# TeensyLED.net
KiCad netlist of a schematic drawn in EAGLE
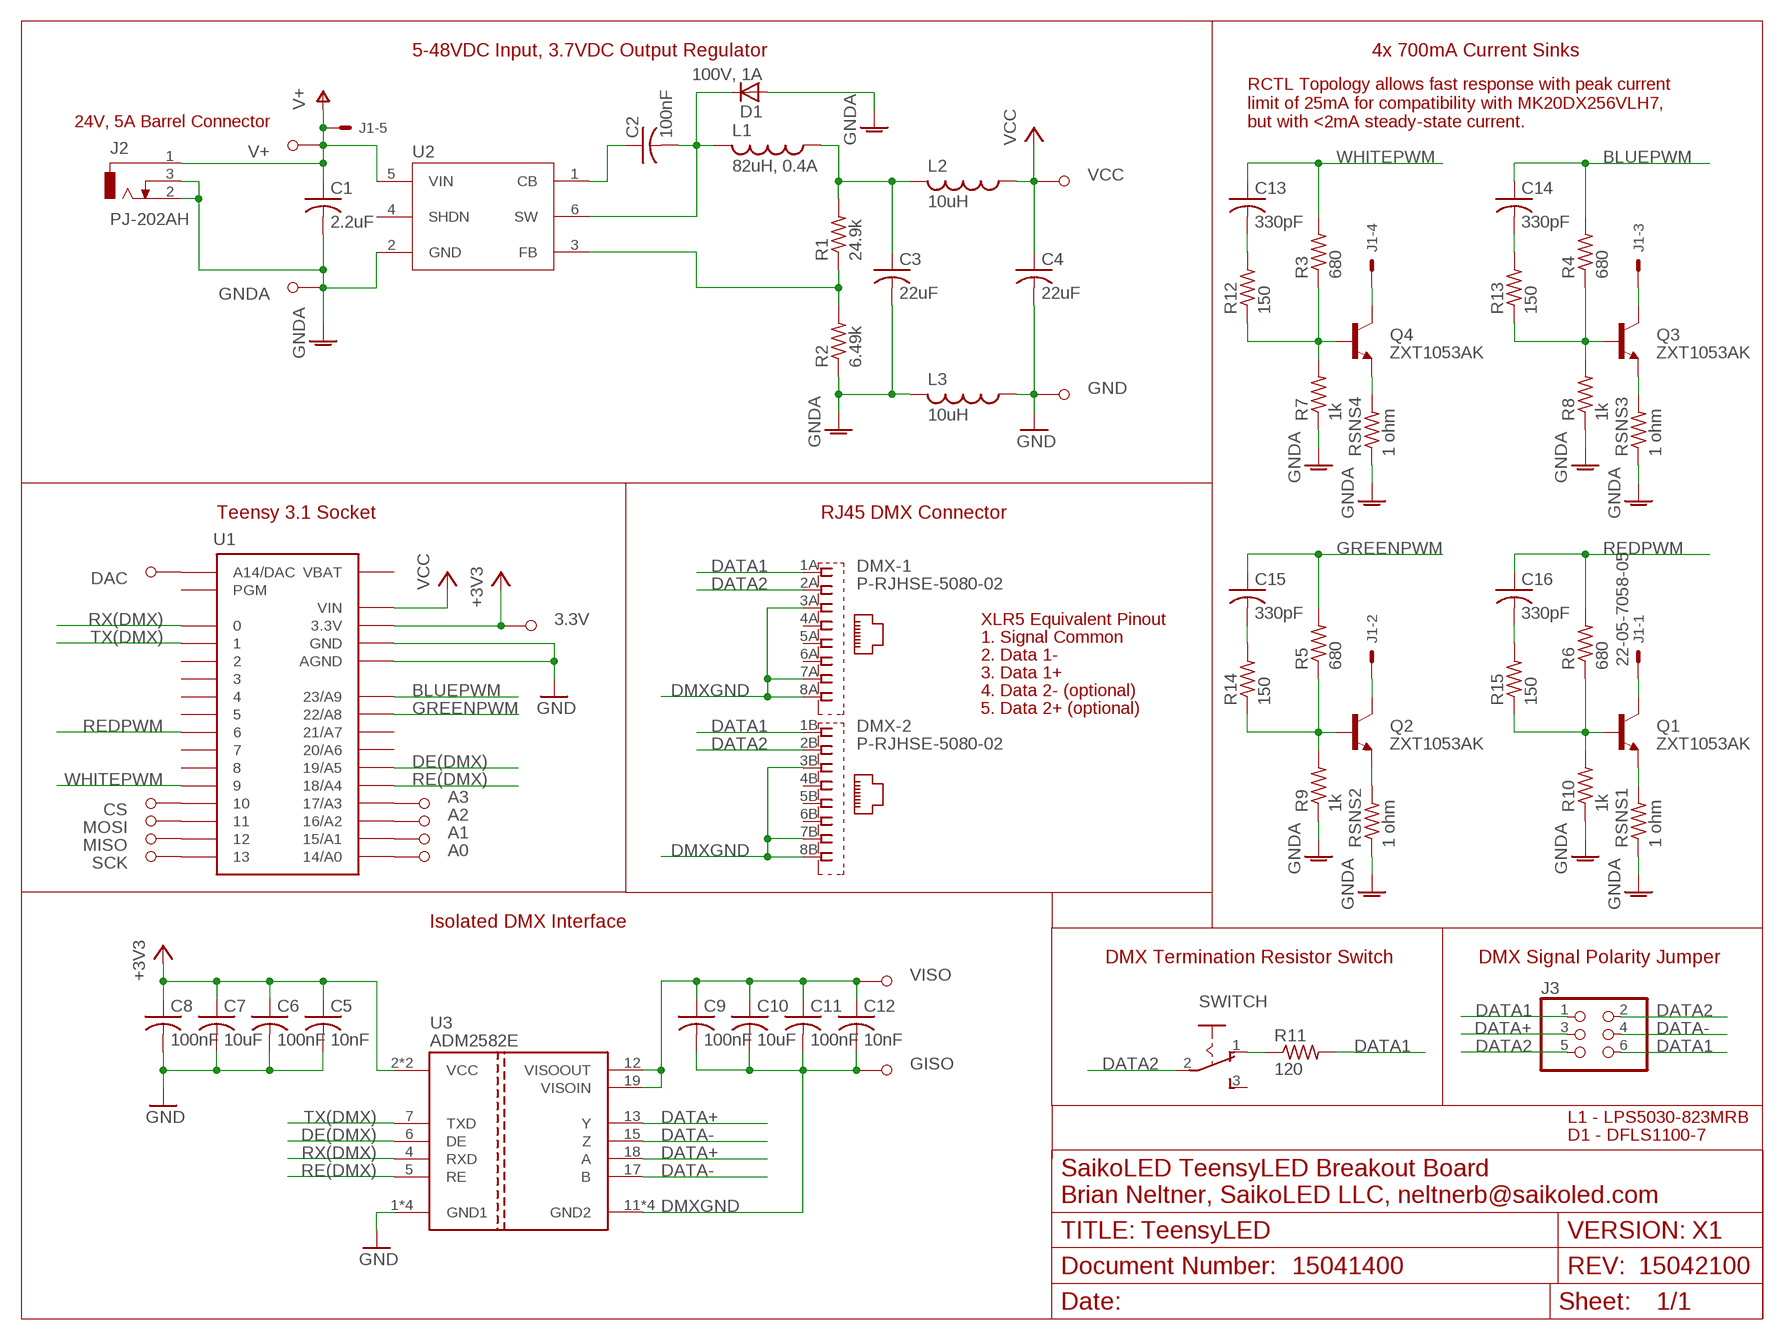
[diagram p0: schematic, sheet 1]

(export (version "E")
  (design (tool "Eeschema 10.0.6"))
  (components
    (comp (ref "3.3V")
      (value "TESTPOINT5019")
      (footprint "eagle-import:5019")
      (libsource (lib "eagle-import") (part "TESTPOINT5019"))
    )
    (comp (ref "A0")
      (value "TESTPOINT5019")
      (footprint "eagle-import:5019")
      (libsource (lib "eagle-import") (part "TESTPOINT5019"))
    )
    (comp (ref "A1")
      (value "TESTPOINT5019")
      (footprint "eagle-import:5019")
      (libsource (lib "eagle-import") (part "TESTPOINT5019"))
    )
    (comp (ref "A2")
      (value "TESTPOINT5019")
      (footprint "eagle-import:5019")
      (libsource (lib "eagle-import") (part "TESTPOINT5019"))
    )
    (comp (ref "A3")
      (value "TESTPOINT5019")
      (footprint "eagle-import:5019")
      (libsource (lib "eagle-import") (part "TESTPOINT5019"))
    )
    (comp (ref "C1")
      (value "2.2uF")
      (footprint "eagle-import:C1210K")
      (libsource (lib "eagle-import") (part "C-USC1210K"))
    )
    (comp (ref "C2")
      (value "100nF")
      (footprint "eagle-import:C0805K")
      (libsource (lib "eagle-import") (part "C-USC0805K"))
    )
    (comp (ref "C3")
      (value "22uF")
      (footprint "eagle-import:C0805K")
      (fields (field (name "MF") "Multicomp Passives") (field (name "MPN") "MCLV4R7M1HB-0513-RH"))
      (libsource (lib "eagle-import") (part "C-USC0805K"))
    )
    (comp (ref "C4")
      (value "22uF")
      (footprint "eagle-import:C0805K")
      (libsource (lib "eagle-import") (part "C-USC0805K"))
    )
    (comp (ref "C5")
      (value "10nF")
      (footprint "eagle-import:C0402PRO")
      (libsource (lib "eagle-import") (part "C-USC0402PRO"))
    )
    (comp (ref "C6")
      (value "100nF")
      (footprint "eagle-import:C0402PRO")
      (libsource (lib "eagle-import") (part "C-USC0402PRO"))
    )
    (comp (ref "C7")
      (value "10uF")
      (footprint "eagle-import:C0402PRO")
      (libsource (lib "eagle-import") (part "C-USC0402PRO"))
    )
    (comp (ref "C8")
      (value "100nF")
      (footprint "eagle-import:C0402PRO")
      (libsource (lib "eagle-import") (part "C-USC0402PRO"))
    )
    (comp (ref "C9")
      (value "100nF")
      (footprint "eagle-import:C0402PRO")
      (libsource (lib "eagle-import") (part "C-USC0402PRO"))
    )
    (comp (ref "C10")
      (value "10uF")
      (footprint "eagle-import:C0402PRO")
      (libsource (lib "eagle-import") (part "C-USC0402PRO"))
    )
    (comp (ref "C11")
      (value "100nF")
      (footprint "eagle-import:C0402PRO")
      (libsource (lib "eagle-import") (part "C-USC0402PRO"))
    )
    (comp (ref "C12")
      (value "10nF")
      (footprint "eagle-import:C0402PRO")
      (libsource (lib "eagle-import") (part "C-USC0402PRO"))
    )
    (comp (ref "C13")
      (value "330pF")
      (footprint "eagle-import:C0402PRO")
      (libsource (lib "eagle-import") (part "C-USC0402PRO"))
    )
    (comp (ref "C14")
      (value "330pF")
      (footprint "eagle-import:C0402PRO")
      (libsource (lib "eagle-import") (part "C-USC0402PRO"))
    )
    (comp (ref "C15")
      (value "330pF")
      (footprint "eagle-import:C0402PRO")
      (libsource (lib "eagle-import") (part "C-USC0402PRO"))
    )
    (comp (ref "C16")
      (value "330pF")
      (footprint "eagle-import:C0402PRO")
      (libsource (lib "eagle-import") (part "C-USC0402PRO"))
    )
    (comp (ref "CS")
      (value "TESTPOINT5019")
      (footprint "eagle-import:5019")
      (libsource (lib "eagle-import") (part "TESTPOINT5019"))
    )
    (comp (ref "D1")
      (value "100V, 1A")
      (footprint "eagle-import:DFLS1100")
      (libsource (lib "eagle-import") (part "DFLS1100"))
    )
    (comp (ref "DAC")
      (value "TESTPOINT5019")
      (footprint "eagle-import:5019")
      (libsource (lib "eagle-import") (part "TESTPOINT5019"))
    )
    (comp (ref "DMX")
      (value "P-RJHSE-5080-02")
      (footprint "eagle-import:P-RJHSE-5080-02")
      (libsource (lib "eagle-import") (part "P-RJHSE-5080-02"))
    )
    (comp (ref "FRAME1")
      (value "LETTER_L")
      (footprint "eagle-import:PCBINFO")
      (libsource (lib "eagle-import") (part "LETTER_L"))
    )
    (comp (ref "GISO")
      (value "TESTPOINT5019")
      (footprint "eagle-import:5019")
      (libsource (lib "eagle-import") (part "TESTPOINT5019"))
    )
    (comp (ref "GND")
      (value "TESTPOINT5019")
      (footprint "eagle-import:5019")
      (libsource (lib "eagle-import") (part "TESTPOINT5019"))
    )
    (comp (ref "GNDA")
      (value "TESTPOINT5019")
      (footprint "eagle-import:5019")
      (libsource (lib "eagle-import") (part "TESTPOINT5019"))
    )
    (comp (ref "J1")
      (value "22-05-7058-05")
      (footprint "eagle-import:7395-05")
      (libsource (lib "eagle-import") (part "22-?-0505-7058"))
    )
    (comp (ref "J2")
      (value "PJ-202AH")
      (footprint "eagle-import:PJ-202AH")
      (libsource (lib "eagle-import") (part "PJ-202AH"))
    )
    (comp (ref "J3")
      (value "PINHD-2X3")
      (footprint "eagle-import:2X03")
      (libsource (lib "eagle-import") (part "PINHD-2X3"))
    )
    (comp (ref "L1")
      (value "82uH, 0.4A")
      (footprint "eagle-import:LPS5030")
      (libsource (lib "eagle-import") (part "L-US"))
    )
    (comp (ref "L2")
      (value "10uH")
      (footprint "eagle-import:L2012C")
      (libsource (lib "eagle-import") (part "rcl_L-USL2012C"))
    )
    (comp (ref "L3")
      (value "10uH")
      (footprint "eagle-import:L2012C")
      (libsource (lib "eagle-import") (part "rcl_L-USL2012C"))
    )
    (comp (ref "MISO")
      (value "TESTPOINT5019")
      (footprint "eagle-import:5019")
      (libsource (lib "eagle-import") (part "TESTPOINT5019"))
    )
    (comp (ref "MOSI")
      (value "TESTPOINT5019")
      (footprint "eagle-import:5019")
      (libsource (lib "eagle-import") (part "TESTPOINT5019"))
    )
    (comp (ref "Q1")
      (value "ZXT1053AK")
      (footprint "eagle-import:TO252")
      (libsource (lib "eagle-import") (part "ZXT1053AK"))
    )
    (comp (ref "Q2")
      (value "ZXT1053AK")
      (footprint "eagle-import:TO252")
      (libsource (lib "eagle-import") (part "ZXT1053AK"))
    )
    (comp (ref "Q3")
      (value "ZXT1053AK")
      (footprint "eagle-import:TO252")
      (libsource (lib "eagle-import") (part "ZXT1053AK"))
    )
    (comp (ref "Q4")
      (value "ZXT1053AK")
      (footprint "eagle-import:TO252")
      (libsource (lib "eagle-import") (part "ZXT1053AK"))
    )
    (comp (ref "R1")
      (value "24.9k")
      (footprint "eagle-import:R0402PRO")
      (fields (field (name "MPN") "BLU0402-9762-BT25W"))
      (libsource (lib "eagle-import") (part "R-US_R0402PRO"))
    )
    (comp (ref "R2")
      (value "6.49k")
      (footprint "eagle-import:R0402PRO")
      (fields (field (name "MPN") "ERJ-3EKF4123V"))
      (libsource (lib "eagle-import") (part "R-US_R0402PRO"))
    )
    (comp (ref "R3")
      (value "680")
      (footprint "eagle-import:R0402PRO")
      (libsource (lib "eagle-import") (part "R-US_R0402PRO"))
    )
    (comp (ref "R4")
      (value "680")
      (footprint "eagle-import:R0402PRO")
      (libsource (lib "eagle-import") (part "R-US_R0402PRO"))
    )
    (comp (ref "R5")
      (value "680")
      (footprint "eagle-import:R0402PRO")
      (libsource (lib "eagle-import") (part "R-US_R0402PRO"))
    )
    (comp (ref "R6")
      (value "680")
      (footprint "eagle-import:R0402PRO")
      (libsource (lib "eagle-import") (part "R-US_R0402PRO"))
    )
    (comp (ref "R7")
      (value "1k")
      (footprint "eagle-import:R0402PRO")
      (libsource (lib "eagle-import") (part "R-US_R0402PRO"))
    )
    (comp (ref "R8")
      (value "1k")
      (footprint "eagle-import:R0402PRO")
      (libsource (lib "eagle-import") (part "R-US_R0402PRO"))
    )
    (comp (ref "R9")
      (value "1k")
      (footprint "eagle-import:R0402PRO")
      (libsource (lib "eagle-import") (part "R-US_R0402PRO"))
    )
    (comp (ref "R10")
      (value "1k")
      (footprint "eagle-import:R0402PRO")
      (libsource (lib "eagle-import") (part "R-US_R0402PRO"))
    )
    (comp (ref "R11")
      (value "120")
      (footprint "eagle-import:R0402PRO")
      (libsource (lib "eagle-import") (part "R-US_R0402PRO"))
    )
    (comp (ref "R12")
      (value "150")
      (footprint "eagle-import:R0402PRO")
      (libsource (lib "eagle-import") (part "R-US_R0402PRO"))
    )
    (comp (ref "R13")
      (value "150")
      (footprint "eagle-import:R0402PRO")
      (libsource (lib "eagle-import") (part "R-US_R0402PRO"))
    )
    (comp (ref "R14")
      (value "150")
      (footprint "eagle-import:R0402PRO")
      (libsource (lib "eagle-import") (part "R-US_R0402PRO"))
    )
    (comp (ref "R15")
      (value "150")
      (footprint "eagle-import:R0402PRO")
      (libsource (lib "eagle-import") (part "R-US_R0402PRO"))
    )
    (comp (ref "RSNS1")
      (value "1 ohm")
      (footprint "eagle-import:R1206")
      (libsource (lib "eagle-import") (part "R-US_R1206"))
    )
    (comp (ref "RSNS2")
      (value "1 ohm")
      (footprint "eagle-import:R1206")
      (libsource (lib "eagle-import") (part "R-US_R1206"))
    )
    (comp (ref "RSNS3")
      (value "1 ohm")
      (footprint "eagle-import:R1206")
      (libsource (lib "eagle-import") (part "R-US_R1206"))
    )
    (comp (ref "RSNS4")
      (value "1 ohm")
      (footprint "eagle-import:R1206")
      (libsource (lib "eagle-import") (part "R-US_R1206"))
    )
    (comp (ref "SCK")
      (value "TESTPOINT5019")
      (footprint "eagle-import:5019")
      (libsource (lib "eagle-import") (part "TESTPOINT5019"))
    )
    (comp (ref "SWITCH")
      (value "M251")
      (footprint "eagle-import:SK-12F17-G")
      (libsource (lib "eagle-import") (part "M251"))
    )
    (comp (ref "U1")
      (value "TEENSY_3.0_BASIC")
      (footprint "eagle-import:TEENSY_3.0_BASIC")
      (libsource (lib "eagle-import") (part "TEENSY_3.0_BASIC"))
    )
    (comp (ref "U2")
      (value "LMR16006YDDCT")
      (footprint "eagle-import:DDC0006A")
      (fields
        (field (name "MANUFACTURER") "Texas Instruments")
        (field (name "PARTNUMBER") "LMR16006YDDC")
        (field (name "MF") "FARNELL")
      )
      (libsource (lib "eagle-import") (part "LMR16006YDDCT"))
    )
    (comp (ref "U3")
      (value "ADM2582E")
      (footprint "eagle-import:SO-20DW")
      (libsource (lib "eagle-import") (part "ADM2582E"))
    )
    (comp (ref "V+")
      (value "TESTPOINT5019")
      (footprint "eagle-import:5019")
      (libsource (lib "eagle-import") (part "TESTPOINT5019"))
    )
    (comp (ref "VCC")
      (value "TESTPOINT5019")
      (footprint "eagle-import:5019")
      (libsource (lib "eagle-import") (part "TESTPOINT5019"))
    )
    (comp (ref "VISO")
      (value "TESTPOINT5019")
      (footprint "eagle-import:5019")
      (libsource (lib "eagle-import") (part "TESTPOINT5019"))
    )
  )
  (nets
    (net (code "1") (name "+3V3") (class "Default")
      (node (ref "3.3V") (pin "P$1") (pinfunction "P$1_P$1") (pintype "passive"))
      (node (ref "C5") (pin "1") (pinfunction "1_1") (pintype "passive"))
      (node (ref "C6") (pin "1") (pinfunction "1_1") (pintype "passive"))
      (node (ref "C7") (pin "1") (pinfunction "1_1") (pintype "passive"))
      (node (ref "C8") (pin "1") (pinfunction "1_1") (pintype "passive"))
      (node (ref "U1") (pin "3.3V") (pinfunction "3.3V_3.3V") (pintype "power_in"))
      (node (ref "U1") (pin "3.3V1") (pinfunction "3.3V_3.3V1") (pintype "power_in"))
      (node (ref "U3") (pin "2") (pinfunction "VCC_2") (pintype "bidirectional"))
      (node (ref "U3") (pin "8") (pinfunction "VCC_8") (pintype "bidirectional"))
    )
    (net (code "2") (name "/BLUEPWM") (class "Default")
      (node (ref "C14") (pin "1") (pinfunction "1_1") (pintype "passive"))
      (node (ref "R4") (pin "2") (pinfunction "2_2") (pintype "passive"))
      (node (ref "U1") (pin "23/A9") (pinfunction "23/A9_23/A9") (pintype "bidirectional"))
    )
    (net (code "3") (name "/DATA+") (class "Default")
      (node (ref "J3") (pin "3") (pinfunction "3_3") (pintype "passive"))
      (node (ref "U3") (pin "13") (pinfunction "Y_13") (pintype "bidirectional"))
      (node (ref "U3") (pin "18") (pinfunction "A_18") (pintype "bidirectional"))
    )
    (net (code "4") (name "/DATA-") (class "Default")
      (node (ref "J3") (pin "4") (pinfunction "4_4") (pintype "passive"))
      (node (ref "U3") (pin "15") (pinfunction "Z_15") (pintype "bidirectional"))
      (node (ref "U3") (pin "17") (pinfunction "B_17") (pintype "bidirectional"))
    )
    (net (code "5") (name "/DATA1") (class "Default")
      (node (ref "DMX") (pin "1A") (pinfunction "1_1A") (pintype "passive"))
      (node (ref "DMX") (pin "1B") (pinfunction "1_1B") (pintype "passive"))
      (node (ref "J3") (pin "1") (pinfunction "1_1") (pintype "passive"))
      (node (ref "J3") (pin "6") (pinfunction "6_6") (pintype "passive"))
      (node (ref "R11") (pin "2") (pinfunction "2_2") (pintype "passive"))
    )
    (net (code "6") (name "/DATA2") (class "Default")
      (node (ref "DMX") (pin "2A") (pinfunction "2_2A") (pintype "passive"))
      (node (ref "DMX") (pin "2B") (pinfunction "2_2B") (pintype "passive"))
      (node (ref "J3") (pin "2") (pinfunction "2_2") (pintype "passive"))
      (node (ref "J3") (pin "5") (pinfunction "5_5") (pintype "passive"))
      (node (ref "SWITCH") (pin "2") (pinfunction "P_2") (pintype "passive"))
    )
    (net (code "7") (name "/DE(DMX)") (class "Default")
      (node (ref "U1") (pin "19/A5") (pinfunction "19/A5_19/A5") (pintype "bidirectional"))
      (node (ref "U3") (pin "6") (pinfunction "DE_6") (pintype "bidirectional"))
    )
    (net (code "8") (name "/DMXGND") (class "Default")
      (node (ref "C10") (pin "2") (pinfunction "2_2") (pintype "passive"))
      (node (ref "C11") (pin "2") (pinfunction "2_2") (pintype "passive"))
      (node (ref "C12") (pin "2") (pinfunction "2_2") (pintype "passive"))
      (node (ref "C9") (pin "2") (pinfunction "2_2") (pintype "passive"))
      (node (ref "DMX") (pin "3A") (pinfunction "3_3A") (pintype "passive"))
      (node (ref "DMX") (pin "3B") (pinfunction "3_3B") (pintype "passive"))
      (node (ref "DMX") (pin "7A") (pinfunction "7_7A") (pintype "passive"))
      (node (ref "DMX") (pin "7B") (pinfunction "7_7B") (pintype "passive"))
      (node (ref "DMX") (pin "8A") (pinfunction "8_8A") (pintype "passive"))
      (node (ref "DMX") (pin "8B") (pinfunction "8_8B") (pintype "passive"))
      (node (ref "GISO") (pin "P$1") (pinfunction "P$1_P$1") (pintype "passive"))
      (node (ref "U3") (pin "11") (pinfunction "GND2_11") (pintype "bidirectional"))
      (node (ref "U3") (pin "14") (pinfunction "GND2_14") (pintype "bidirectional"))
      (node (ref "U3") (pin "16") (pinfunction "GND2_16") (pintype "bidirectional"))
      (node (ref "U3") (pin "20") (pinfunction "GND2_20") (pintype "bidirectional"))
    )
    (net (code "9") (name "/GREENPWM") (class "Default")
      (node (ref "C15") (pin "1") (pinfunction "1_1") (pintype "passive"))
      (node (ref "R5") (pin "2") (pinfunction "2_2") (pintype "passive"))
      (node (ref "U1") (pin "22/A8") (pinfunction "22/A8_22/A8") (pintype "bidirectional"))
    )
    (net (code "10") (name "/RE(DMX)") (class "Default")
      (node (ref "U1") (pin "18/A4") (pinfunction "18/A4_18/A4") (pintype "bidirectional"))
      (node (ref "U3") (pin "5") (pinfunction "RE_5") (pintype "bidirectional"))
    )
    (net (code "11") (name "/REDPWM") (class "Default")
      (node (ref "C16") (pin "1") (pinfunction "1_1") (pintype "passive"))
      (node (ref "R6") (pin "2") (pinfunction "2_2") (pintype "passive"))
      (node (ref "U1") (pin "6") (pinfunction "6_6") (pintype "bidirectional"))
    )
    (net (code "12") (name "/RX(DMX)") (class "Default")
      (node (ref "U1") (pin "0") (pinfunction "0_0") (pintype "bidirectional"))
      (node (ref "U3") (pin "4") (pinfunction "RXD_4") (pintype "bidirectional"))
    )
    (net (code "13") (name "/TX(DMX)") (class "Default")
      (node (ref "U1") (pin "1") (pinfunction "1_1") (pintype "bidirectional"))
      (node (ref "U3") (pin "7") (pinfunction "TXD_7") (pintype "bidirectional"))
    )
    (net (code "14") (name "/VBAT") (class "Default")
      (node (ref "U1") (pin "VBAT") (pinfunction "VBAT_VBAT") (pintype "power_in"))
    )
    (net (code "15") (name "/WHITEPWM") (class "Default")
      (node (ref "C13") (pin "1") (pinfunction "1_1") (pintype "passive"))
      (node (ref "R3") (pin "2") (pinfunction "2_2") (pintype "passive"))
      (node (ref "U1") (pin "9") (pinfunction "9_9") (pintype "bidirectional"))
    )
    (net (code "16") (name "GND") (class "Default")
      (node (ref "C4") (pin "2") (pinfunction "2_2") (pintype "passive"))
      (node (ref "C5") (pin "2") (pinfunction "2_2") (pintype "passive"))
      (node (ref "C6") (pin "2") (pinfunction "2_2") (pintype "passive"))
      (node (ref "C7") (pin "2") (pinfunction "2_2") (pintype "passive"))
      (node (ref "C8") (pin "2") (pinfunction "2_2") (pintype "passive"))
      (node (ref "GND") (pin "P$1") (pinfunction "P$1_P$1") (pintype "passive"))
      (node (ref "L3") (pin "1") (pinfunction "1_1") (pintype "passive"))
      (node (ref "U1") (pin "AGND") (pinfunction "AGND_AGND") (pintype "power_in"))
      (node (ref "U1") (pin "GND") (pinfunction "GND_GND") (pintype "power_in"))
      (node (ref "U1") (pin "GND1") (pinfunction "GND_GND1") (pintype "power_in"))
      (node (ref "U3") (pin "1") (pinfunction "GND1_1") (pintype "bidirectional"))
      (node (ref "U3") (pin "10") (pinfunction "GND1_10") (pintype "bidirectional"))
      (node (ref "U3") (pin "3") (pinfunction "GND1_3") (pintype "bidirectional"))
      (node (ref "U3") (pin "9") (pinfunction "GND1_9") (pintype "bidirectional"))
    )
    (net (code "17") (name "GNDA") (class "Default")
      (node (ref "C1") (pin "2") (pinfunction "2_2") (pintype "passive"))
      (node (ref "C3") (pin "2") (pinfunction "2_2") (pintype "passive"))
      (node (ref "D1") (pin "A") (pinfunction "A_A") (pintype "passive"))
      (node (ref "GNDA") (pin "P$1") (pinfunction "P$1_P$1") (pintype "passive"))
      (node (ref "J2") (pin "2") (pinfunction "3_2") (pintype "passive"))
      (node (ref "J2") (pin "3") (pinfunction "2_3") (pintype "passive"))
      (node (ref "L3") (pin "2") (pinfunction "2_2") (pintype "passive"))
      (node (ref "R10") (pin "1") (pinfunction "1_1") (pintype "passive"))
      (node (ref "R2") (pin "1") (pinfunction "1_1") (pintype "passive"))
      (node (ref "R7") (pin "1") (pinfunction "1_1") (pintype "passive"))
      (node (ref "R8") (pin "1") (pinfunction "1_1") (pintype "passive"))
      (node (ref "R9") (pin "1") (pinfunction "1_1") (pintype "passive"))
      (node (ref "RSNS1") (pin "1") (pinfunction "1_1") (pintype "passive"))
      (node (ref "RSNS2") (pin "1") (pinfunction "1_1") (pintype "passive"))
      (node (ref "RSNS3") (pin "1") (pinfunction "1_1") (pintype "passive"))
      (node (ref "RSNS4") (pin "1") (pinfunction "1_1") (pintype "passive"))
      (node (ref "U2") (pin "2") (pinfunction "GND_2") (pintype "power_in"))
    )
    (net (code "18") (name "Net-(A0-PadP$1)") (class "Default")
      (node (ref "A0") (pin "P$1") (pinfunction "P$1_P$1") (pintype "passive"))
      (node (ref "U1") (pin "14/A0") (pinfunction "14/A0_14/A0") (pintype "bidirectional"))
    )
    (net (code "19") (name "Net-(A1-PadP$1)") (class "Default")
      (node (ref "A1") (pin "P$1") (pinfunction "P$1_P$1") (pintype "passive"))
      (node (ref "U1") (pin "15/A1") (pinfunction "15/A1_15/A1") (pintype "bidirectional"))
    )
    (net (code "20") (name "Net-(A2-PadP$1)") (class "Default")
      (node (ref "A2") (pin "P$1") (pinfunction "P$1_P$1") (pintype "passive"))
      (node (ref "U1") (pin "16/A2") (pinfunction "16/A2_16/A2") (pintype "bidirectional"))
    )
    (net (code "21") (name "Net-(A3-PadP$1)") (class "Default")
      (node (ref "A3") (pin "P$1") (pinfunction "P$1_P$1") (pintype "passive"))
      (node (ref "U1") (pin "17/A3") (pinfunction "17/A3_17/A3") (pintype "bidirectional"))
    )
    (net (code "22") (name "Net-(C13-Pad2)") (class "Default")
      (node (ref "C13") (pin "2") (pinfunction "2_2") (pintype "passive"))
      (node (ref "R12") (pin "2") (pinfunction "2_2") (pintype "passive"))
    )
    (net (code "23") (name "Net-(C14-Pad2)") (class "Default")
      (node (ref "C14") (pin "2") (pinfunction "2_2") (pintype "passive"))
      (node (ref "R13") (pin "2") (pinfunction "2_2") (pintype "passive"))
    )
    (net (code "24") (name "Net-(C15-Pad2)") (class "Default")
      (node (ref "C15") (pin "2") (pinfunction "2_2") (pintype "passive"))
      (node (ref "R14") (pin "2") (pinfunction "2_2") (pintype "passive"))
    )
    (net (code "25") (name "Net-(C16-Pad2)") (class "Default")
      (node (ref "C16") (pin "2") (pinfunction "2_2") (pintype "passive"))
      (node (ref "R15") (pin "2") (pinfunction "2_2") (pintype "passive"))
    )
    (net (code "26") (name "Net-(CS-PadP$1)") (class "Default")
      (node (ref "CS") (pin "P$1") (pinfunction "P$1_P$1") (pintype "passive"))
      (node (ref "U1") (pin "10") (pinfunction "10_10") (pintype "bidirectional"))
    )
    (net (code "27") (name "Net-(J1A-S)") (class "Default")
      (node (ref "J1") (pin "1") (pinfunction "S_1") (pintype "passive"))
      (node (ref "Q1") (pin "C") (pinfunction "C_C") (pintype "passive"))
    )
    (net (code "28") (name "Net-(J1B-S)") (class "Default")
      (node (ref "J1") (pin "2") (pinfunction "S_2") (pintype "passive"))
      (node (ref "Q2") (pin "C") (pinfunction "C_C") (pintype "passive"))
    )
    (net (code "29") (name "Net-(J1C-S)") (class "Default")
      (node (ref "J1") (pin "3") (pinfunction "S_3") (pintype "passive"))
      (node (ref "Q3") (pin "C") (pinfunction "C_C") (pintype "passive"))
    )
    (net (code "30") (name "Net-(J1D-S)") (class "Default")
      (node (ref "J1") (pin "4") (pinfunction "S_4") (pintype "passive"))
      (node (ref "Q4") (pin "C") (pinfunction "C_C") (pintype "passive"))
    )
    (net (code "31") (name "Net-(L1-1)") (class "Default")
      (node (ref "C3") (pin "1") (pinfunction "1_1") (pintype "passive"))
      (node (ref "L1") (pin "P$1") (pinfunction "1_P$1") (pintype "passive"))
      (node (ref "L2") (pin "2") (pinfunction "2_2") (pintype "passive"))
      (node (ref "R1") (pin "2") (pinfunction "2_2") (pintype "passive"))
    )
    (net (code "32") (name "Net-(L1-2)") (class "Default")
      (node (ref "C2") (pin "2") (pinfunction "2_2") (pintype "passive"))
      (node (ref "D1") (pin "C") (pinfunction "C_C") (pintype "passive"))
      (node (ref "L1") (pin "P$2") (pinfunction "2_P$2") (pintype "passive"))
      (node (ref "U2") (pin "6") (pinfunction "SW_6") (pintype "power_in"))
    )
    (net (code "33") (name "Net-(MISO-PadP$1)") (class "Default")
      (node (ref "MISO") (pin "P$1") (pinfunction "P$1_P$1") (pintype "passive"))
      (node (ref "U1") (pin "12") (pinfunction "12_12") (pintype "bidirectional"))
    )
    (net (code "34") (name "Net-(MOSI-PadP$1)") (class "Default")
      (node (ref "MOSI") (pin "P$1") (pinfunction "P$1_P$1") (pintype "passive"))
      (node (ref "U1") (pin "11") (pinfunction "11_11") (pintype "bidirectional"))
    )
    (net (code "35") (name "Net-(Q1-PadB)") (class "Default")
      (node (ref "Q1") (pin "B") (pinfunction "B_B") (pintype "passive"))
      (node (ref "R10") (pin "2") (pinfunction "2_2") (pintype "passive"))
      (node (ref "R15") (pin "1") (pinfunction "1_1") (pintype "passive"))
      (node (ref "R6") (pin "1") (pinfunction "1_1") (pintype "passive"))
    )
    (net (code "36") (name "Net-(Q1-PadE)") (class "Default")
      (node (ref "Q1") (pin "E") (pinfunction "E_E") (pintype "passive"))
      (node (ref "RSNS1") (pin "2") (pinfunction "2_2") (pintype "passive"))
    )
    (net (code "37") (name "Net-(Q2-PadB)") (class "Default")
      (node (ref "Q2") (pin "B") (pinfunction "B_B") (pintype "passive"))
      (node (ref "R14") (pin "1") (pinfunction "1_1") (pintype "passive"))
      (node (ref "R5") (pin "1") (pinfunction "1_1") (pintype "passive"))
      (node (ref "R9") (pin "2") (pinfunction "2_2") (pintype "passive"))
    )
    (net (code "38") (name "Net-(Q2-PadE)") (class "Default")
      (node (ref "Q2") (pin "E") (pinfunction "E_E") (pintype "passive"))
      (node (ref "RSNS2") (pin "2") (pinfunction "2_2") (pintype "passive"))
    )
    (net (code "39") (name "Net-(Q3-PadB)") (class "Default")
      (node (ref "Q3") (pin "B") (pinfunction "B_B") (pintype "passive"))
      (node (ref "R13") (pin "1") (pinfunction "1_1") (pintype "passive"))
      (node (ref "R4") (pin "1") (pinfunction "1_1") (pintype "passive"))
      (node (ref "R8") (pin "2") (pinfunction "2_2") (pintype "passive"))
    )
    (net (code "40") (name "Net-(Q3-PadE)") (class "Default")
      (node (ref "Q3") (pin "E") (pinfunction "E_E") (pintype "passive"))
      (node (ref "RSNS3") (pin "2") (pinfunction "2_2") (pintype "passive"))
    )
    (net (code "41") (name "Net-(Q4-PadB)") (class "Default")
      (node (ref "Q4") (pin "B") (pinfunction "B_B") (pintype "passive"))
      (node (ref "R12") (pin "1") (pinfunction "1_1") (pintype "passive"))
      (node (ref "R3") (pin "1") (pinfunction "1_1") (pintype "passive"))
      (node (ref "R7") (pin "2") (pinfunction "2_2") (pintype "passive"))
    )
    (net (code "42") (name "Net-(Q4-PadE)") (class "Default")
      (node (ref "Q4") (pin "E") (pinfunction "E_E") (pintype "passive"))
      (node (ref "RSNS4") (pin "2") (pinfunction "2_2") (pintype "passive"))
    )
    (net (code "43") (name "Net-(SCK-PadP$1)") (class "Default")
      (node (ref "SCK") (pin "P$1") (pinfunction "P$1_P$1") (pintype "passive"))
      (node (ref "U1") (pin "13") (pinfunction "13_13") (pintype "bidirectional"))
    )
    (net (code "44") (name "Net-(SWITCH-O)") (class "Default")
      (node (ref "R11") (pin "1") (pinfunction "1_1") (pintype "passive"))
      (node (ref "SWITCH") (pin "1") (pinfunction "O_1") (pintype "passive"))
    )
    (net (code "45") (name "Net-(U1-A14{slash}DAC)") (class "Default")
      (node (ref "DAC") (pin "P$1") (pinfunction "P$1_P$1") (pintype "passive"))
      (node (ref "U1") (pin "RESET") (pinfunction "A14/DAC_RESET") (pintype "bidirectional"))
    )
    (net (code "46") (name "Net-(U2-CB)") (class "Default")
      (node (ref "C2") (pin "1") (pinfunction "1_1") (pintype "passive"))
      (node (ref "U2") (pin "1") (pinfunction "CB_1") (pintype "output"))
    )
    (net (code "47") (name "Net-(U2-FB)") (class "Default")
      (node (ref "R1") (pin "1") (pinfunction "1_1") (pintype "passive"))
      (node (ref "R2") (pin "2") (pinfunction "2_2") (pintype "passive"))
      (node (ref "U2") (pin "3") (pinfunction "FB_3") (pintype "input"))
    )
    (net (code "48") (name "Net-(U3-VISOIN)") (class "Default")
      (node (ref "C10") (pin "1") (pinfunction "1_1") (pintype "passive"))
      (node (ref "C11") (pin "1") (pinfunction "1_1") (pintype "passive"))
      (node (ref "C12") (pin "1") (pinfunction "1_1") (pintype "passive"))
      (node (ref "C9") (pin "1") (pinfunction "1_1") (pintype "passive"))
      (node (ref "U3") (pin "12") (pinfunction "VISOOUT_12") (pintype "bidirectional"))
      (node (ref "U3") (pin "19") (pinfunction "VISOIN_19") (pintype "bidirectional"))
      (node (ref "VISO") (pin "P$1") (pinfunction "P$1_P$1") (pintype "passive"))
    )
    (net (code "49") (name "V+") (class "Default")
      (node (ref "C1") (pin "1") (pinfunction "1_1") (pintype "passive"))
      (node (ref "J1") (pin "5") (pinfunction "S_5") (pintype "passive"))
      (node (ref "J2") (pin "1") (pinfunction "1_1") (pintype "passive"))
      (node (ref "U2") (pin "5") (pinfunction "VIN_5") (pintype "power_in"))
      (node (ref "V+") (pin "P$1") (pinfunction "P$1_P$1") (pintype "passive"))
    )
    (net (code "50") (name "VCC") (class "Default")
      (node (ref "C4") (pin "1") (pinfunction "1_1") (pintype "passive"))
      (node (ref "L2") (pin "1") (pinfunction "1_1") (pintype "passive"))
      (node (ref "U1") (pin "VIN") (pinfunction "VIN_VIN") (pintype "power_in"))
      (node (ref "VCC") (pin "P$1") (pinfunction "P$1_P$1") (pintype "passive"))
    )
    (net (code "51") (name "unconnected-(DMXA-4-Pad4A)") (class "Default")
      (node (ref "DMX") (pin "4A") (pinfunction "4_4A") (pintype "passive"))
    )
    (net (code "52") (name "unconnected-(DMXA-5-Pad5A)") (class "Default")
      (node (ref "DMX") (pin "5A") (pinfunction "5_5A") (pintype "passive"))
    )
    (net (code "53") (name "unconnected-(DMXA-6-Pad6A)") (class "Default")
      (node (ref "DMX") (pin "6A") (pinfunction "6_6A") (pintype "passive"))
    )
    (net (code "54") (name "unconnected-(DMXB-4-Pad4B)") (class "Default")
      (node (ref "DMX") (pin "4B") (pinfunction "4_4B") (pintype "passive"))
    )
    (net (code "55") (name "unconnected-(DMXB-5-Pad5B)") (class "Default")
      (node (ref "DMX") (pin "5B") (pinfunction "5_5B") (pintype "passive"))
    )
    (net (code "56") (name "unconnected-(DMXB-6-Pad6B)") (class "Default")
      (node (ref "DMX") (pin "6B") (pinfunction "6_6B") (pintype "passive"))
    )
    (net (code "57") (name "unconnected-(SWITCH-S-Pad3)") (class "Default")
      (node (ref "SWITCH") (pin "3") (pinfunction "S_3") (pintype "passive"))
    )
    (net (code "58") (name "unconnected-(U1-Pad2)") (class "Default")
      (node (ref "U1") (pin "2") (pinfunction "2_2") (pintype "bidirectional"))
    )
    (net (code "59") (name "unconnected-(U1-Pad3)") (class "Default")
      (node (ref "U1") (pin "3") (pinfunction "3_3") (pintype "bidirectional"))
    )
    (net (code "60") (name "unconnected-(U1-Pad4)") (class "Default")
      (node (ref "U1") (pin "4") (pinfunction "4_4") (pintype "bidirectional"))
    )
    (net (code "61") (name "unconnected-(U1-Pad5)") (class "Default")
      (node (ref "U1") (pin "5") (pinfunction "5_5") (pintype "bidirectional"))
    )
    (net (code "62") (name "unconnected-(U1-Pad7)") (class "Default")
      (node (ref "U1") (pin "7") (pinfunction "7_7") (pintype "bidirectional"))
    )
    (net (code "63") (name "unconnected-(U1-Pad8)") (class "Default")
      (node (ref "U1") (pin "8") (pinfunction "8_8") (pintype "bidirectional"))
    )
    (net (code "64") (name "unconnected-(U1-Pad20{slash}A6)") (class "Default")
      (node (ref "U1") (pin "20/A6") (pinfunction "20/A6_20/A6") (pintype "bidirectional"))
    )
    (net (code "65") (name "unconnected-(U1-Pad21{slash}A7)") (class "Default")
      (node (ref "U1") (pin "21/A7") (pinfunction "21/A7_21/A7") (pintype "bidirectional"))
    )
    (net (code "66") (name "unconnected-(U1-PadPGM)") (class "Default")
      (node (ref "U1") (pin "PGM") (pinfunction "PGM_PGM") (pintype "bidirectional"))
    )
    (net (code "67") (name "unconnected-(U2-SHDN-Pad4)") (class "Default")
      (node (ref "U2") (pin "4") (pinfunction "SHDN_4") (pintype "input"))
    )
  )
)
